# schematic_Func_Gen.net
KiCad netlist of a schematic drawn in Altium Designer
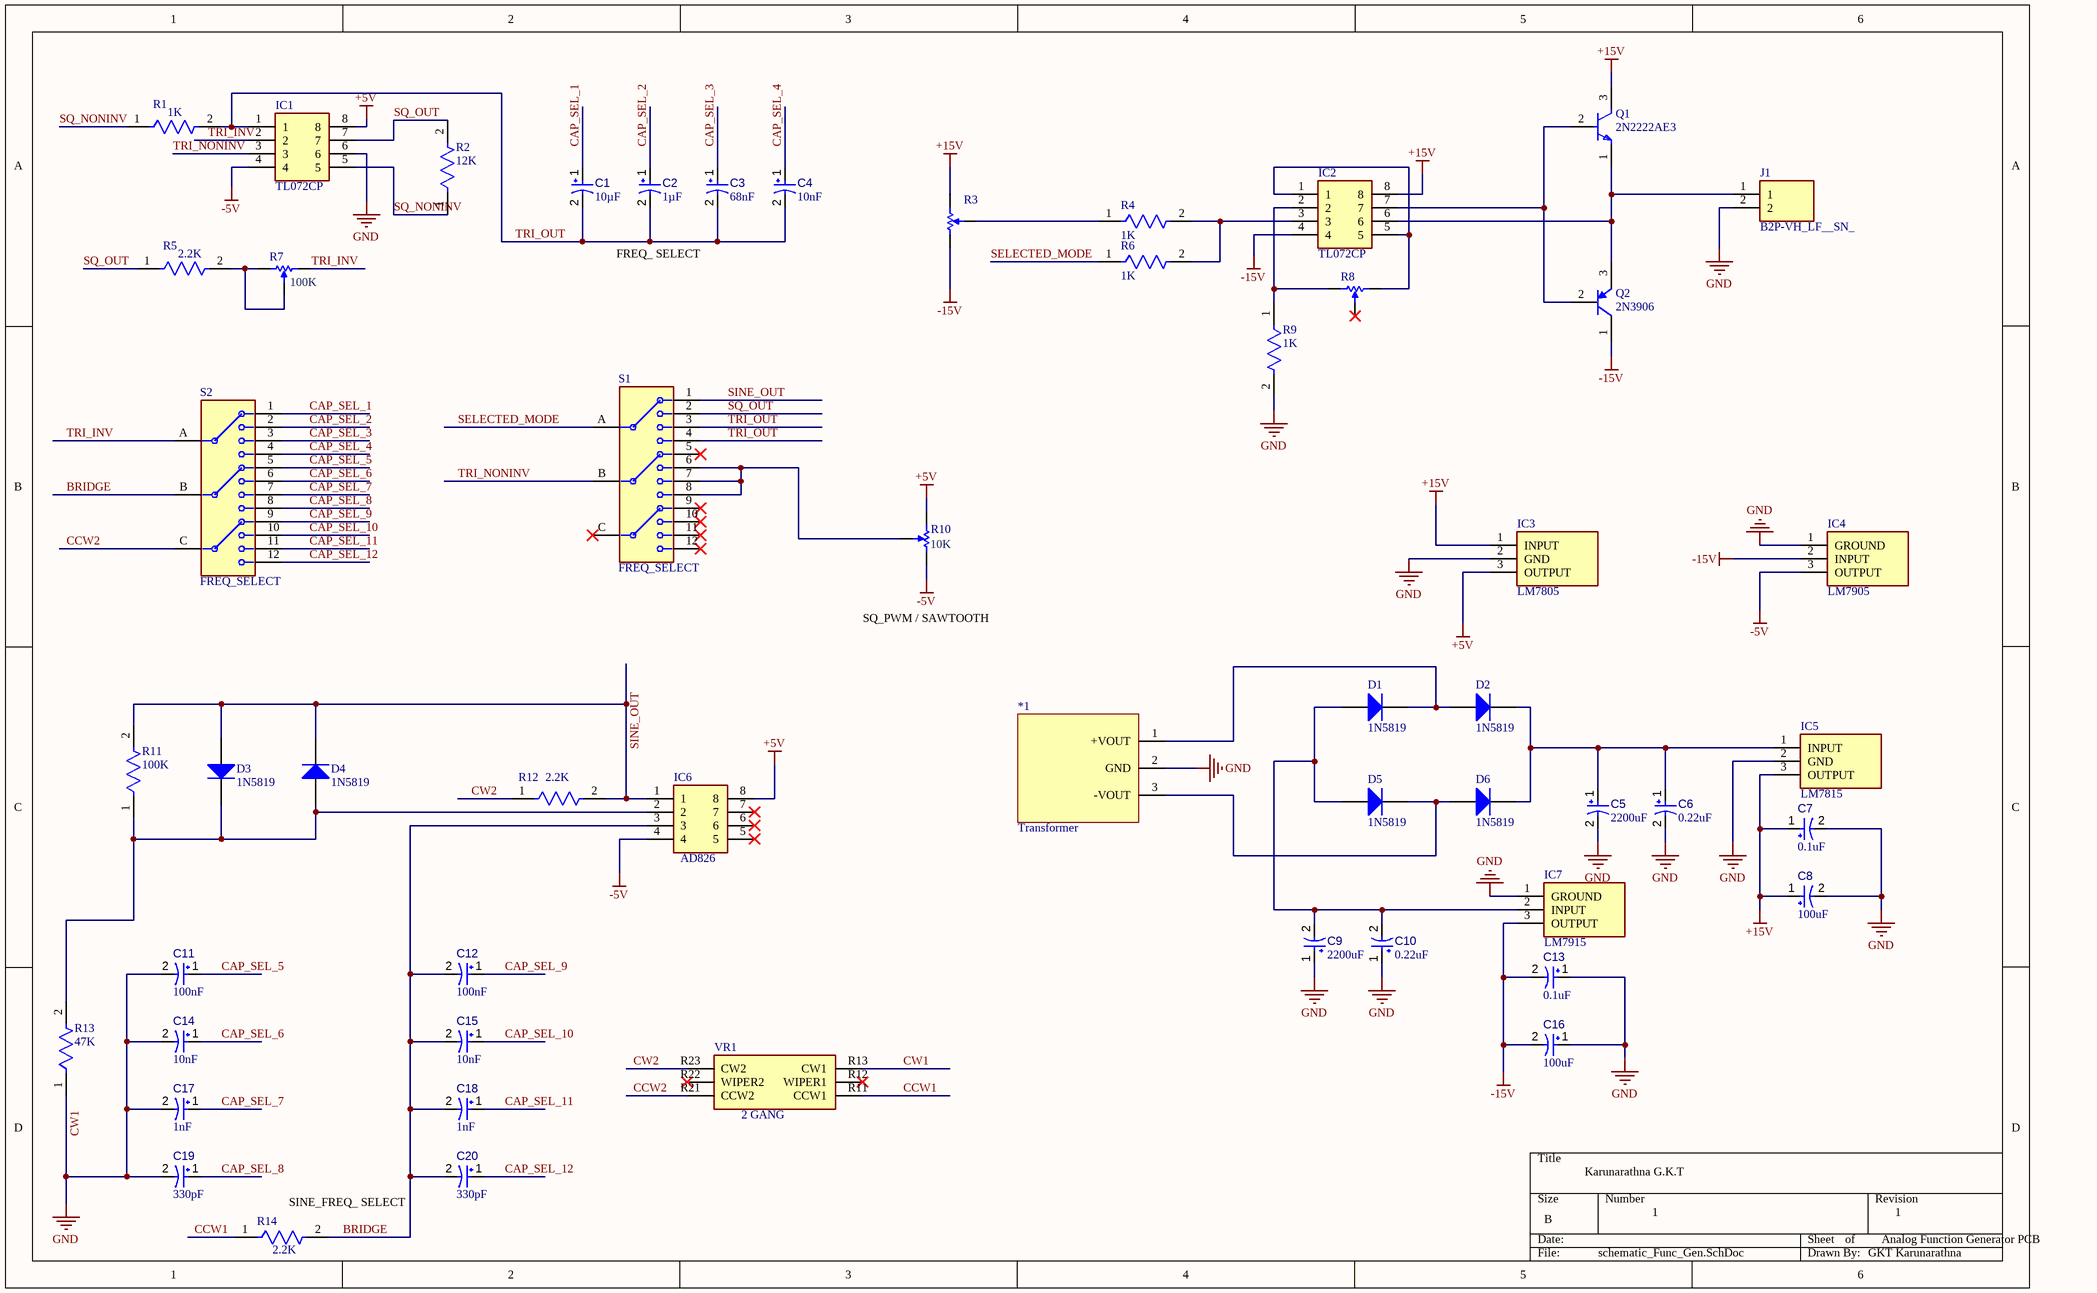
[diagram p0: schematic_Func_Gen.SchDoc]

(export (version "E")
  (design (tool "Eeschema 10.0.6"))
  (components
    (comp (ref "*1")
      (value "Transformer")
      (footprint "transformer")
      (libsource (lib "Schlib") (part "Transformer"))
    )
    (comp (ref "C1")
      (value "10µF")
      (footprint "CAPPR65-500-1250X1000X1350")
      (description "Aluminum Electrolytic Capacitor, 220 uF, +/- 20%, 50 V, -40 to 85 degC, 2-Pin THD, RoHS, Bulk")
      (fields (field (name "MANUFACTURER") "Panasonic") (field (name "TOLERANCE") "20%"))
      (libsource (lib "") (part "CAP-P-2_1"))
    )
    (comp (ref "C2")
      (value "1µF")
      (footprint "CAPPR65-500-1250X1000X1350")
      (description "Aluminum Electrolytic Capacitor, 10 uF, +/- 20%, 50 V, -40 to 85 degC, 2-Pin THD, RoHS, Bulk")
      (fields (field (name "MANUFACTURER") "Panasonic") (field (name "TOLERANCE") "20%"))
      (libsource (lib "") (part "CAP-P-2_1"))
    )
    (comp (ref "C3")
      (value "68nF")
      (footprint "CAPPR65-500-1250X1000X1350")
      (description "Aluminum Electrolytic Capacitor, 220 uF, +/- 20%, 50 V, -40 to 85 degC, 2-Pin THD, RoHS, Bulk")
      (fields (field (name "MANUFACTURER") "Panasonic") (field (name "TOLERANCE") "20%"))
      (libsource (lib "") (part "CAP-P-2_1"))
    )
    (comp (ref "C4")
      (value "10nF")
      (footprint "CAPPR65-500-1250X1000X1350")
      (description "Aluminum Electrolytic Capacitor, 220 uF, +/- 20%, 50 V, -40 to 85 degC, 2-Pin THD, RoHS, Bulk")
      (fields (field (name "MANUFACTURER") "Panasonic") (field (name "TOLERANCE") "20%"))
      (libsource (lib "") (part "CAP-P-2_1"))
    )
    (comp (ref "C5")
      (value "2200uF")
      (footprint "CAPPR65-500-1250X1000X1350")
      (description "Aluminum Electrolytic Capacitor, 220 uF, +/- 20%, 50 V, -40 to 85 degC, 2-Pin THD, RoHS, Bulk")
      (fields (field (name "MANUFACTURER") "Panasonic") (field (name "TOLERANCE") "20%"))
      (libsource (lib "") (part "CAP-P-2_1"))
    )
    (comp (ref "C6")
      (value "0.22uF")
      (footprint "CAPPR65-500-1250X1000X1350")
      (description "Aluminum Electrolytic Capacitor, 220 uF, +/- 20%, 50 V, -40 to 85 degC, 2-Pin THD, RoHS, Bulk")
      (fields (field (name "MANUFACTURER") "Panasonic") (field (name "TOLERANCE") "20%"))
      (libsource (lib "") (part "CAP-P-2_1"))
    )
    (comp (ref "C7")
      (value "0.1uF")
      (footprint "CAPPR65-500-1250X1000X1350")
      (description "Aluminum Electrolytic Capacitor, 220 uF, +/- 20%, 50 V, -40 to 85 degC, 2-Pin THD, RoHS, Bulk")
      (fields (field (name "MANUFACTURER") "Panasonic") (field (name "TOLERANCE") "20%"))
      (libsource (lib "") (part "CAP-P-2_2"))
    )
    (comp (ref "C8")
      (value "100uF")
      (footprint "CAPPR65-500-1250X1000X1350")
      (description "Aluminum Electrolytic Capacitor, 220 uF, +/- 20%, 50 V, -40 to 85 degC, 2-Pin THD, RoHS, Bulk")
      (fields (field (name "MANUFACTURER") "Panasonic") (field (name "TOLERANCE") "20%"))
      (libsource (lib "") (part "CAP-P-2_2"))
    )
    (comp (ref "C9")
      (value "2200uF")
      (footprint "CAPPR65-500-1250X1000X1350")
      (description "Aluminum Electrolytic Capacitor, 220 uF, +/- 20%, 50 V, -40 to 85 degC, 2-Pin THD, RoHS, Bulk")
      (fields (field (name "MANUFACTURER") "Panasonic") (field (name "TOLERANCE") "20%"))
      (libsource (lib "") (part "CAP-P-2_3"))
    )
    (comp (ref "C10")
      (value "0.22uF")
      (footprint "CAPPR65-500-1250X1000X1350")
      (description "Aluminum Electrolytic Capacitor, 220 uF, +/- 20%, 50 V, -40 to 85 degC, 2-Pin THD, RoHS, Bulk")
      (fields (field (name "MANUFACTURER") "Panasonic") (field (name "TOLERANCE") "20%"))
      (libsource (lib "") (part "CAP-P-2_3"))
    )
    (comp (ref "C11")
      (value "100nF")
      (footprint "CAPPR65-500-1250X1000X1350")
      (description "Aluminum Electrolytic Capacitor, 220 uF, +/- 20%, 50 V, -40 to 85 degC, 2-Pin THD, RoHS, Bulk")
      (fields (field (name "MANUFACTURER") "Panasonic") (field (name "TOLERANCE") "20%"))
      (libsource (lib "Kavija Karunarathna") (part "CAP-P-2"))
    )
    (comp (ref "C12")
      (value "100nF")
      (footprint "CAPPR65-500-1250X1000X1350")
      (description "Aluminum Electrolytic Capacitor, 220 uF, +/- 20%, 50 V, -40 to 85 degC, 2-Pin THD, RoHS, Bulk")
      (fields (field (name "MANUFACTURER") "Panasonic") (field (name "TOLERANCE") "20%"))
      (libsource (lib "Kavija Karunarathna") (part "CAP-P-2"))
    )
    (comp (ref "C13")
      (value "0.1uF")
      (footprint "CAPPR65-500-1250X1000X1350")
      (description "Aluminum Electrolytic Capacitor, 220 uF, +/- 20%, 50 V, -40 to 85 degC, 2-Pin THD, RoHS, Bulk")
      (fields (field (name "MANUFACTURER") "Panasonic") (field (name "TOLERANCE") "20%"))
      (libsource (lib "Kavija Karunarathna") (part "CAP-P-2"))
    )
    (comp (ref "C14")
      (value "10nF")
      (footprint "CAPPR65-500-1250X1000X1350")
      (description "Aluminum Electrolytic Capacitor, 220 uF, +/- 20%, 50 V, -40 to 85 degC, 2-Pin THD, RoHS, Bulk")
      (fields (field (name "MANUFACTURER") "Panasonic") (field (name "TOLERANCE") "20%"))
      (libsource (lib "Kavija Karunarathna") (part "CAP-P-2"))
    )
    (comp (ref "C15")
      (value "10nF")
      (footprint "CAPPR65-500-1250X1000X1350")
      (description "Aluminum Electrolytic Capacitor, 220 uF, +/- 20%, 50 V, -40 to 85 degC, 2-Pin THD, RoHS, Bulk")
      (fields (field (name "MANUFACTURER") "Panasonic") (field (name "TOLERANCE") "20%"))
      (libsource (lib "Kavija Karunarathna") (part "CAP-P-2"))
    )
    (comp (ref "C16")
      (value "100uF")
      (footprint "CAPPR65-500-1250X1000X1350")
      (description "Aluminum Electrolytic Capacitor, 220 uF, +/- 20%, 50 V, -40 to 85 degC, 2-Pin THD, RoHS, Bulk")
      (fields (field (name "MANUFACTURER") "Panasonic") (field (name "TOLERANCE") "20%"))
      (libsource (lib "Kavija Karunarathna") (part "CAP-P-2"))
    )
    (comp (ref "C17")
      (value "1nF")
      (footprint "CAPPR65-500-1250X1000X1350")
      (description "Aluminum Electrolytic Capacitor, 220 uF, +/- 20%, 50 V, -40 to 85 degC, 2-Pin THD, RoHS, Bulk")
      (fields (field (name "MANUFACTURER") "Panasonic") (field (name "TOLERANCE") "20%"))
      (libsource (lib "Kavija Karunarathna") (part "CAP-P-2"))
    )
    (comp (ref "C18")
      (value "1nF")
      (footprint "CAPPR65-500-1250X1000X1350")
      (description "Aluminum Electrolytic Capacitor, 220 uF, +/- 20%, 50 V, -40 to 85 degC, 2-Pin THD, RoHS, Bulk")
      (fields (field (name "MANUFACTURER") "Panasonic") (field (name "TOLERANCE") "20%"))
      (libsource (lib "Kavija Karunarathna") (part "CAP-P-2"))
    )
    (comp (ref "C19")
      (value "330pF")
      (footprint "CAPPR65-500-1250X1000X1350")
      (description "Aluminum Electrolytic Capacitor, 220 uF, +/- 20%, 50 V, -40 to 85 degC, 2-Pin THD, RoHS, Bulk")
      (fields (field (name "MANUFACTURER") "Panasonic") (field (name "TOLERANCE") "20%"))
      (libsource (lib "Kavija Karunarathna") (part "CAP-P-2"))
    )
    (comp (ref "C20")
      (value "330pF")
      (footprint "CAPPR65-500-1250X1000X1350")
      (description "Aluminum Electrolytic Capacitor, 220 uF, +/- 20%, 50 V, -40 to 85 degC, 2-Pin THD, RoHS, Bulk")
      (fields (field (name "MANUFACTURER") "Panasonic") (field (name "TOLERANCE") "20%"))
      (libsource (lib "Kavija Karunarathna") (part "CAP-P-2"))
    )
    (comp (ref "D1")
      (value "1N5819")
      (footprint "ONSC-AXIAL_LEAD-2-59-10_P")
      (description "Low Drop Power Schottky Rectifier, 40 V, 1 A, 2-Pin DO-41, RoHS")
      (fields (field (name "MANUFACTURER") "ON Semiconductor"))
      (libsource (lib "Kavija Karunarathna") (part "D-AK-2"))
    )
    (comp (ref "D2")
      (value "1N5819")
      (footprint "ONSC-AXIAL_LEAD-2-59-10_P")
      (description "Low Drop Power Schottky Rectifier, 40 V, 1 A, 2-Pin DO-41, RoHS")
      (fields (field (name "MANUFACTURER") "ON Semiconductor"))
      (libsource (lib "Kavija Karunarathna") (part "D-AK-2"))
    )
    (comp (ref "D3")
      (value "1N5819")
      (footprint "ONSC-AXIAL_LEAD-2-59-10_P")
      (description "Low Drop Power Schottky Rectifier, 40 V, 1 A, 2-Pin DO-41, RoHS")
      (fields (field (name "MANUFACTURER") "ON Semiconductor"))
      (libsource (lib "Kavija Karunarathna") (part "D-AK-2"))
    )
    (comp (ref "D4")
      (value "1N5819")
      (footprint "ONSC-AXIAL_LEAD-2-59-10_P")
      (description "Low Drop Power Schottky Rectifier, 40 V, 1 A, 2-Pin DO-41, RoHS")
      (fields (field (name "MANUFACTURER") "ON Semiconductor"))
      (libsource (lib "Kavija Karunarathna") (part "D-AK-2"))
    )
    (comp (ref "D5")
      (value "1N5819")
      (footprint "ONSC-AXIAL_LEAD-2-59-10_P")
      (description "Low Drop Power Schottky Rectifier, 40 V, 1 A, 2-Pin DO-41, RoHS")
      (fields (field (name "MANUFACTURER") "ON Semiconductor"))
      (libsource (lib "Kavija Karunarathna") (part "D-AK-2"))
    )
    (comp (ref "D6")
      (value "1N5819")
      (footprint "ONSC-AXIAL_LEAD-2-59-10_P")
      (description "Low Drop Power Schottky Rectifier, 40 V, 1 A, 2-Pin DO-41, RoHS")
      (fields (field (name "MANUFACTURER") "ON Semiconductor"))
      (libsource (lib "Kavija Karunarathna") (part "D-AK-2"))
    )
    (comp (ref "IC1")
      (value "TL072CP")
      (footprint "SamacSys:DIPS762W70P254L1016H510Q8N")
      (description "Integrated Circuit")
      (fields
        (field (name "MANUFACTURER_PART_NUMBER") "1-2199298-2")
        (field (name "MOUSER PART NUMBER") "571-1-2199298-2")
      )
      (libsource (lib "*") (part "1-2199298-2"))
    )
    (comp (ref "IC2")
      (value "TL072CP")
      (footprint "SamacSys:DIPS762W70P254L1016H510Q8N")
      (description "Integrated Circuit")
      (fields
        (field (name "MANUFACTURER_PART_NUMBER") "1-2199298-2")
        (field (name "MOUSER PART NUMBER") "571-1-2199298-2")
      )
      (libsource (lib "*") (part "1-2199298-2"))
    )
    (comp (ref "IC3")
      (value "LM7805")
      (footprint "SamacSys:TO254P470X990X1900-3P")
      (description "Integrated Circuit")
      (libsource (lib "*") (part "LM7805"))
    )
    (comp (ref "IC4")
      (value "LM7905")
      (footprint "SamacSys:TO254P470X1028X1955-3P")
      (description "Integrated Circuit")
      (fields
        (field (name "MANUFACTURER_PART_NUMBER") "LM7905CT")
        (field (name "MOUSER PART NUMBER") "926-LM7905CT")
      )
      (libsource (lib "*") (part "LM7905CT"))
    )
    (comp (ref "IC5")
      (value "LM7815")
      (footprint "SamacSys:TO254P470X990X1900-3P")
      (description "Integrated Circuit")
      (fields (field (name "MANUFACTURER_PART_NUMBER") "LM7805"))
      (libsource (lib "*") (part "LM7805"))
    )
    (comp (ref "IC6")
      (value "AD826")
      (footprint "SamacSys:DIPS762W70P254L1016H510Q8N")
      (description "Integrated Circuit")
      (fields
        (field (name "MANUFACTURER_PART_NUMBER") "1-2199298-2")
        (field (name "MOUSER PART NUMBER") "571-1-2199298-2")
      )
      (libsource (lib "*") (part "1-2199298-2"))
    )
    (comp (ref "IC7")
      (value "LM7915")
      (footprint "SamacSys:TO254P470X1028X1955-3P")
      (description "Integrated Circuit")
      (fields
        (field (name "MANUFACTURER_PART_NUMBER") "LM7905CT")
        (field (name "MOUSER PART NUMBER") "926-LM7905CT")
      )
      (libsource (lib "*") (part "LM7905CT"))
    )
    (comp (ref "J1")
      (value "B2P-VH_LF__SN_")
      (footprint "SamacSys:HDRV2W114P0X396_1X2_786X850X1090P")
      (description "Connector")
      (fields (field (name "MANUFACTURER_PART_NUMBER") "B2P-VH(LF)(SN)"))
      (libsource (lib "*") (part "B2P-VH_LF__SN_"))
    )
    (comp (ref "Q1")
      (value "2N2222AE3")
      (footprint "FP-TO-18-MFG")
      (description "2N2222AE3 Bipolar (BJT) Transistor NPN 50V 800mA 500mW Through Hole TO-18")
      (libsource (lib "Altium Content Vault") (part "0adf1720dacd0b636365b40e7c27fbb"))
    )
    (comp (ref "Q2")
      (value "2N3906")
      (footprint "ONSC-TO-92-3-29-11_AM_BL")
      (description "Amplifier Transistor, PNP Silicon, 3-Pin TO-92, Pb-Free, Ammo Box")
      (fields (field (name "PARTNUMBER") "BC557AZL1G") (field (name "MANUFACTURER") "On Semiconductor"))
      (libsource (lib "Altium Content Vault") (part "ONSC-PNP-C1B2E3-3"))
    )
    (comp (ref "R1")
      (value "1K")
      (footprint "FP-RLR07-MFG")
      (description "RLR07C15R0FSB14 Res Metal Film 15 Ohm 1% 1/4W ±100ppm/°C 0.001% Conformal AXL Thru-Hole Bulk")
      (fields (field (name "TOLERANCE") "1%"))
      (libsource (lib "Altium Content Vault") (part "1029c3af85768c4190bb7ad29bc67b5"))
    )
    (comp (ref "R2")
      (value "12K")
      (footprint "FP-RLR07-MFG")
      (description "RLR07C15R0FSB14 Res Metal Film 15 Ohm 1% 1/4W ±100ppm/°C 0.001% Conformal AXL Thru-Hole Bulk")
      (fields (field (name "TOLERANCE") "1%"))
      (libsource (lib "Altium Content Vault") (part "1029c3af85768c4190bb7ad29bc67b5"))
    )
    (comp (ref "R3")
      (value "TC33X-2-103E")
      (footprint "BOUR-TC33X-2_V")
      (description "Trimming Potentiometer, 10000 Ohm, -40 to 100 degC, 3-Pin SMD, RoHS, Tape and Reel")
      (fields (field (name "TOLERANCE") "25%") (field (name "MANUFACTURER") "Bourns"))
      (libsource (lib "Kavija Karunarathna") (part "RES-ADJ-3_A"))
    )
    (comp (ref "R4")
      (value "1K")
      (footprint "FP-RLR07-MFG")
      (description "RLR07C15R0FSB14 Res Metal Film 15 Ohm 1% 1/4W ±100ppm/°C 0.001% Conformal AXL Thru-Hole Bulk")
      (fields (field (name "TOLERANCE") "1%"))
      (libsource (lib "Altium Content Vault") (part "1029c3af85768c4190bb7ad29bc67b5"))
    )
    (comp (ref "R5")
      (value "2.2K")
      (footprint "FP-RLR07-MFG")
      (description "RLR07C15R0FSB14 Res Metal Film 15 Ohm 1% 1/4W ±100ppm/°C 0.001% Conformal AXL Thru-Hole Bulk")
      (fields (field (name "TOLERANCE") "1%"))
      (libsource (lib "Altium Content Vault") (part "1029c3af85768c4190bb7ad29bc67b5"))
    )
    (comp (ref "R6")
      (value "1K")
      (footprint "FP-RLR07-MFG")
      (description "RLR07C15R0FSB14 Res Metal Film 15 Ohm 1% 1/4W ±100ppm/°C 0.001% Conformal AXL Thru-Hole Bulk")
      (fields (field (name "TOLERANCE") "1%"))
      (libsource (lib "Altium Content Vault") (part "1029c3af85768c4190bb7ad29bc67b5"))
    )
    (comp (ref "R7")
      (value "TC33X-2-103E")
      (footprint "BOUR-TC33X-2_V")
      (description "Trimming Potentiometer, 10000 Ohm, -40 to 100 degC, 3-Pin SMD, RoHS, Tape and Reel")
      (fields (field (name "TOLERANCE") "25%") (field (name "MANUFACTURER") "Bourns"))
      (libsource (lib "Kavija Karunarathna") (part "RES-ADJ-3_A"))
    )
    (comp (ref "R8")
      (value "TC33X-2-103E")
      (footprint "BOUR-TC33X-2_V")
      (description "Trimming Potentiometer, 10000 Ohm, -40 to 100 degC, 3-Pin SMD, RoHS, Tape and Reel")
      (fields (field (name "TOLERANCE") "25%") (field (name "MANUFACTURER") "Bourns"))
      (libsource (lib "Kavija Karunarathna") (part "RES-ADJ-3_A"))
    )
    (comp (ref "R9")
      (value "1K")
      (footprint "FP-RLR07-MFG")
      (description "RLR07C15R0FSB14 Res Metal Film 15 Ohm 1% 1/4W ±100ppm/°C 0.001% Conformal AXL Thru-Hole Bulk")
      (fields (field (name "TOLERANCE") "1%"))
      (libsource (lib "Altium Content Vault") (part "1029c3af85768c4190bb7ad29bc67b5"))
    )
    (comp (ref "R10")
      (value "TC33X-2-103E")
      (footprint "BOUR-TC33X-2_V")
      (description "Trimming Potentiometer, 10000 Ohm, -40 to 100 degC, 3-Pin SMD, RoHS, Tape and Reel")
      (fields (field (name "TOLERANCE") "25%") (field (name "MANUFACTURER") "Bourns"))
      (libsource (lib "Kavija Karunarathna") (part "RES-ADJ-3_A"))
    )
    (comp (ref "R11")
      (value "100K")
      (footprint "FP-RLR07-MFG")
      (description "RLR07C15R0FSB14 Res Metal Film 15 Ohm 1% 1/4W ±100ppm/°C 0.001% Conformal AXL Thru-Hole Bulk")
      (fields (field (name "TOLERANCE") "1%"))
      (libsource (lib "Altium Content Vault") (part "1029c3af85768c4190bb7ad29bc67b5"))
    )
    (comp (ref "R12")
      (value "2.2K")
      (footprint "FP-RLR07-MFG")
      (description "RLR07C15R0FSB14 Res Metal Film 15 Ohm 1% 1/4W ±100ppm/°C 0.001% Conformal AXL Thru-Hole Bulk")
      (fields (field (name "TOLERANCE") "1%"))
      (libsource (lib "Altium Content Vault") (part "1029c3af85768c4190bb7ad29bc67b5"))
    )
    (comp (ref "R13")
      (value "47K")
      (footprint "FP-RLR07-MFG")
      (description "RLR07C15R0FSB14 Res Metal Film 15 Ohm 1% 1/4W ±100ppm/°C 0.001% Conformal AXL Thru-Hole Bulk")
      (fields (field (name "TOLERANCE") "1%"))
      (libsource (lib "Altium Content Vault") (part "1029c3af85768c4190bb7ad29bc67b5"))
    )
    (comp (ref "R14")
      (value "2.2K")
      (footprint "FP-RLR07-MFG")
      (description "RLR07C15R0FSB14 Res Metal Film 15 Ohm 1% 1/4W ±100ppm/°C 0.001% Conformal AXL Thru-Hole Bulk")
      (fields (field (name "TOLERANCE") "1%"))
      (libsource (lib "Altium Content Vault") (part "1029c3af85768c4190bb7ad29bc67b5"))
    )
    (comp (ref "S1")
      (value "FREQ_SELECT")
      (footprint "SW_A30403RNCQ")
      (description "Rotary Switch 4 Position 3P4T 2.5A (AC), 350mA (DC) 125 VAC Panel Mount, Through Hole")
      (fields (field (name "MF") "C&K") (field (name "MP") "A30403RNCQ"))
      (libsource (lib "Schlib") (part "A30403RNCQ"))
    )
    (comp (ref "S2")
      (value "FREQ_SELECT")
      (footprint "SW_A30403RNCQ")
      (description "Rotary Switch 4 Position 3P4T 2.5A (AC), 350mA (DC) 125 VAC Panel Mount, Through Hole")
      (fields (field (name "MF") "C&K") (field (name "MP") "A30403RNCQ"))
      (libsource (lib "Schlib") (part "A30403RNCQ"))
    )
    (comp (ref "VR1")
      (value "2 GANG")
      (footprint "SamacSys:PDB182K220K104B")
      (description "Variable Resistor")
      (fields
        (field (name "MANUFACTURER_PART_NUMBER") "PDB182-K220K-104B")
        (field (name "MOUSER PART NUMBER") "652-PDB182-K220K104B")
      )
      (libsource (lib "*") (part "PDB182-K220K-104B"))
    )
  )
  (nets
    (net (code "1") (name "+5V") (class "Default")
      (node (ref "IC1") (pin "8") (pinfunction "8_8") (pintype "passive"))
      (node (ref "IC3") (pin "3") (pinfunction "OUTPUT_3") (pintype "passive"))
      (node (ref "IC6") (pin "8") (pinfunction "8_8") (pintype "passive"))
      (node (ref "R10") (pin "1") (pinfunction "1_1") (pintype "passive"))
    )
    (net (code "2") (name "+15V") (class "Default")
      (node (ref "C7") (pin "1") (pinfunction "1_1") (pintype "passive"))
      (node (ref "C8") (pin "1") (pinfunction "1_1") (pintype "passive"))
      (node (ref "IC2") (pin "8") (pinfunction "8_8") (pintype "passive"))
      (node (ref "IC3") (pin "1") (pinfunction "INPUT_1") (pintype "passive"))
      (node (ref "IC5") (pin "3") (pinfunction "OUTPUT_3") (pintype "passive"))
      (node (ref "Q1") (pin "3") (pinfunction "C_3") (pintype "passive"))
      (node (ref "R3") (pin "3") (pinfunction "3_3") (pintype "passive"))
    )
    (net (code "3") (name "-5V") (class "Default")
      (node (ref "IC1") (pin "4") (pinfunction "4_4") (pintype "passive"))
      (node (ref "IC4") (pin "3") (pinfunction "OUTPUT_3") (pintype "passive"))
      (node (ref "IC6") (pin "4") (pinfunction "4_4") (pintype "passive"))
      (node (ref "R10") (pin "3") (pinfunction "3_3") (pintype "passive"))
    )
    (net (code "4") (name "-15V") (class "Default")
      (node (ref "C13") (pin "2") (pinfunction "2_2") (pintype "passive"))
      (node (ref "C16") (pin "2") (pinfunction "2_2") (pintype "passive"))
      (node (ref "IC2") (pin "4") (pinfunction "4_4") (pintype "passive"))
      (node (ref "IC4") (pin "2") (pinfunction "INPUT_2") (pintype "passive"))
      (node (ref "IC7") (pin "3") (pinfunction "OUTPUT_3") (pintype "passive"))
      (node (ref "Q2") (pin "1") (pinfunction "C_1") (pintype "passive"))
      (node (ref "R3") (pin "1") (pinfunction "1_1") (pintype "passive"))
    )
    (net (code "5") (name "/BRIDGE") (class "Default")
      (node (ref "C12") (pin "2") (pinfunction "2_2") (pintype "passive"))
      (node (ref "C15") (pin "2") (pinfunction "2_2") (pintype "passive"))
      (node (ref "C18") (pin "2") (pinfunction "2_2") (pintype "passive"))
      (node (ref "C20") (pin "2") (pinfunction "2_2") (pintype "passive"))
      (node (ref "IC6") (pin "3") (pinfunction "3_3") (pintype "passive"))
      (node (ref "R14") (pin "2") (pinfunction "2_2") (pintype "passive"))
      (node (ref "S2") (pin "B") (pinfunction "B_B") (pintype "passive"))
    )
    (net (code "6") (name "/CAP_SEL_1") (class "Default")
      (node (ref "C1") (pin "1") (pinfunction "1_1") (pintype "passive"))
      (node (ref "S2") (pin "1") (pinfunction "1_1") (pintype "passive"))
    )
    (net (code "7") (name "/CAP_SEL_2") (class "Default")
      (node (ref "C2") (pin "1") (pinfunction "1_1") (pintype "passive"))
      (node (ref "S2") (pin "2") (pinfunction "2_2") (pintype "passive"))
    )
    (net (code "8") (name "/CAP_SEL_3") (class "Default")
      (node (ref "C3") (pin "1") (pinfunction "1_1") (pintype "passive"))
      (node (ref "S2") (pin "3") (pinfunction "3_3") (pintype "passive"))
    )
    (net (code "9") (name "/CAP_SEL_4") (class "Default")
      (node (ref "C4") (pin "1") (pinfunction "1_1") (pintype "passive"))
      (node (ref "S2") (pin "4") (pinfunction "4_4") (pintype "passive"))
    )
    (net (code "10") (name "/CAP_SEL_5") (class "Default")
      (node (ref "C11") (pin "1") (pinfunction "1_1") (pintype "passive"))
      (node (ref "S2") (pin "5") (pinfunction "5_5") (pintype "passive"))
    )
    (net (code "11") (name "/CAP_SEL_6") (class "Default")
      (node (ref "C14") (pin "1") (pinfunction "1_1") (pintype "passive"))
      (node (ref "S2") (pin "6") (pinfunction "6_6") (pintype "passive"))
    )
    (net (code "12") (name "/CAP_SEL_7") (class "Default")
      (node (ref "C17") (pin "1") (pinfunction "1_1") (pintype "passive"))
      (node (ref "S2") (pin "7") (pinfunction "7_7") (pintype "passive"))
    )
    (net (code "13") (name "/CAP_SEL_8") (class "Default")
      (node (ref "C19") (pin "1") (pinfunction "1_1") (pintype "passive"))
      (node (ref "S2") (pin "8") (pinfunction "8_8") (pintype "passive"))
    )
    (net (code "14") (name "/CAP_SEL_9") (class "Default")
      (node (ref "C12") (pin "1") (pinfunction "1_1") (pintype "passive"))
      (node (ref "S2") (pin "9") (pinfunction "9_9") (pintype "passive"))
    )
    (net (code "15") (name "/CAP_SEL_10") (class "Default")
      (node (ref "C15") (pin "1") (pinfunction "1_1") (pintype "passive"))
      (node (ref "S2") (pin "10") (pinfunction "10_10") (pintype "passive"))
    )
    (net (code "16") (name "/CAP_SEL_11") (class "Default")
      (node (ref "C18") (pin "1") (pinfunction "1_1") (pintype "passive"))
      (node (ref "S2") (pin "11") (pinfunction "11_11") (pintype "passive"))
    )
    (net (code "17") (name "/CAP_SEL_12") (class "Default")
      (node (ref "C20") (pin "1") (pinfunction "1_1") (pintype "passive"))
      (node (ref "S2") (pin "12") (pinfunction "12_12") (pintype "passive"))
    )
    (net (code "18") (name "/CCW1") (class "Default")
      (node (ref "R14") (pin "1") (pinfunction "1_1") (pintype "passive"))
      (node (ref "VR1") (pin "R11") (pinfunction "CCW1_R11") (pintype "passive"))
    )
    (net (code "19") (name "/CCW2") (class "Default")
      (node (ref "S2") (pin "C") (pinfunction "C_C") (pintype "passive"))
      (node (ref "VR1") (pin "R21") (pinfunction "CCW2_R21") (pintype "passive"))
    )
    (net (code "20") (name "/CW2") (class "Default")
      (node (ref "R12") (pin "1") (pinfunction "1_1") (pintype "passive"))
      (node (ref "VR1") (pin "R23") (pinfunction "CW2_R23") (pintype "passive"))
    )
    (net (code "21") (name "/SELECTED_MODE") (class "Default")
      (node (ref "R6") (pin "1") (pinfunction "1_1") (pintype "passive"))
      (node (ref "S1") (pin "A") (pinfunction "A_A") (pintype "passive"))
    )
    (net (code "22") (name "/SINE_OUT") (class "Default")
      (node (ref "D3") (pin "1") (pinfunction "A_1") (pintype "passive"))
      (node (ref "D4") (pin "2") (pinfunction "K_2") (pintype "passive"))
      (node (ref "IC6") (pin "1") (pinfunction "1_1") (pintype "passive"))
      (node (ref "R11") (pin "2") (pinfunction "2_2") (pintype "passive"))
      (node (ref "R12") (pin "2") (pinfunction "2_2") (pintype "passive"))
      (node (ref "S1") (pin "1") (pinfunction "1_1") (pintype "passive"))
    )
    (net (code "23") (name "/SQ_NONINV") (class "Default")
      (node (ref "IC1") (pin "5") (pinfunction "5_5") (pintype "passive"))
      (node (ref "R1") (pin "1") (pinfunction "1_1") (pintype "passive"))
      (node (ref "R2") (pin "1") (pinfunction "1_1") (pintype "passive"))
    )
    (net (code "24") (name "/SQ_OUT") (class "Default")
      (node (ref "IC1") (pin "7") (pinfunction "7_7") (pintype "passive"))
      (node (ref "R2") (pin "2") (pinfunction "2_2") (pintype "passive"))
      (node (ref "R5") (pin "1") (pinfunction "1_1") (pintype "passive"))
      (node (ref "S1") (pin "2") (pinfunction "2_2") (pintype "passive"))
    )
    (net (code "25") (name "/TRI_INV") (class "Default")
      (node (ref "IC1") (pin "2") (pinfunction "2_2") (pintype "passive"))
      (node (ref "R7") (pin "3") (pinfunction "3_3") (pintype "passive"))
      (node (ref "S2") (pin "A") (pinfunction "A_A") (pintype "passive"))
    )
    (net (code "26") (name "/TRI_NONINV") (class "Default")
      (node (ref "IC1") (pin "3") (pinfunction "3_3") (pintype "passive"))
      (node (ref "S1") (pin "B") (pinfunction "B_B") (pintype "passive"))
    )
    (net (code "27") (name "/TRI_OUT") (class "Default")
      (node (ref "C1") (pin "2") (pinfunction "2_2") (pintype "passive"))
      (node (ref "C2") (pin "2") (pinfunction "2_2") (pintype "passive"))
      (node (ref "C3") (pin "2") (pinfunction "2_2") (pintype "passive"))
      (node (ref "C4") (pin "2") (pinfunction "2_2") (pintype "passive"))
      (node (ref "IC1") (pin "1") (pinfunction "1_1") (pintype "passive"))
      (node (ref "R1") (pin "2") (pinfunction "2_2") (pintype "passive"))
      (node (ref "S1") (pin "3") (pinfunction "3_3") (pintype "passive"))
      (node (ref "S1") (pin "4") (pinfunction "4_4") (pintype "passive"))
    )
    (net (code "28") (name "GND") (class "Default")
      (node (ref "*1") (pin "2") (pinfunction "GND_2") (pintype "passive"))
      (node (ref "C10") (pin "1") (pinfunction "1_1") (pintype "passive"))
      (node (ref "C11") (pin "2") (pinfunction "2_2") (pintype "passive"))
      (node (ref "C13") (pin "1") (pinfunction "1_1") (pintype "passive"))
      (node (ref "C14") (pin "2") (pinfunction "2_2") (pintype "passive"))
      (node (ref "C16") (pin "1") (pinfunction "1_1") (pintype "passive"))
      (node (ref "C17") (pin "2") (pinfunction "2_2") (pintype "passive"))
      (node (ref "C19") (pin "2") (pinfunction "2_2") (pintype "passive"))
      (node (ref "C5") (pin "2") (pinfunction "2_2") (pintype "passive"))
      (node (ref "C6") (pin "2") (pinfunction "2_2") (pintype "passive"))
      (node (ref "C7") (pin "2") (pinfunction "2_2") (pintype "passive"))
      (node (ref "C8") (pin "2") (pinfunction "2_2") (pintype "passive"))
      (node (ref "C9") (pin "1") (pinfunction "1_1") (pintype "passive"))
      (node (ref "IC1") (pin "6") (pinfunction "6_6") (pintype "passive"))
      (node (ref "IC3") (pin "2") (pinfunction "GND_2") (pintype "passive"))
      (node (ref "IC4") (pin "1") (pinfunction "GROUND_1") (pintype "passive"))
      (node (ref "IC5") (pin "2") (pinfunction "GND_2") (pintype "passive"))
      (node (ref "IC7") (pin "1") (pinfunction "GROUND_1") (pintype "passive"))
      (node (ref "J1") (pin "2") (pinfunction "2_2") (pintype "passive"))
      (node (ref "R13") (pin "1") (pinfunction "1_1") (pintype "passive"))
      (node (ref "R9") (pin "2") (pinfunction "2_2") (pintype "passive"))
      (node (ref "VR1") (pin "R13") (pinfunction "CW1_R13") (pintype "passive"))
    )
    (net (code "29") (name "Net-(*1-+VOUT)") (class "Default")
      (node (ref "*1") (pin "1") (pinfunction "+VOUT_1") (pintype "passive"))
      (node (ref "D1") (pin "2") (pinfunction "K_2") (pintype "passive"))
      (node (ref "D2") (pin "1") (pinfunction "A_1") (pintype "passive"))
    )
    (net (code "30") (name "Net-(*1--VOUT)") (class "Default")
      (node (ref "*1") (pin "3") (pinfunction "-VOUT_3") (pintype "passive"))
      (node (ref "D5") (pin "2") (pinfunction "K_2") (pintype "passive"))
      (node (ref "D6") (pin "1") (pinfunction "A_1") (pintype "passive"))
    )
    (net (code "31") (name "Net-(D1-A)") (class "Default")
      (node (ref "C10") (pin "2") (pinfunction "2_2") (pintype "passive"))
      (node (ref "C9") (pin "2") (pinfunction "2_2") (pintype "passive"))
      (node (ref "D1") (pin "1") (pinfunction "A_1") (pintype "passive"))
      (node (ref "D5") (pin "1") (pinfunction "A_1") (pintype "passive"))
      (node (ref "IC7") (pin "2") (pinfunction "INPUT_2") (pintype "passive"))
    )
    (net (code "32") (name "Net-(D2-K)") (class "Default")
      (node (ref "C5") (pin "1") (pinfunction "1_1") (pintype "passive"))
      (node (ref "C6") (pin "1") (pinfunction "1_1") (pintype "passive"))
      (node (ref "D2") (pin "2") (pinfunction "K_2") (pintype "passive"))
      (node (ref "D6") (pin "2") (pinfunction "K_2") (pintype "passive"))
      (node (ref "IC5") (pin "1") (pinfunction "INPUT_1") (pintype "passive"))
    )
    (net (code "33") (name "Net-(D3-K)") (class "Default")
      (node (ref "D3") (pin "2") (pinfunction "K_2") (pintype "passive"))
      (node (ref "D4") (pin "1") (pinfunction "A_1") (pintype "passive"))
      (node (ref "IC6") (pin "2") (pinfunction "2_2") (pintype "passive"))
      (node (ref "R11") (pin "1") (pinfunction "1_1") (pintype "passive"))
      (node (ref "R13") (pin "2") (pinfunction "2_2") (pintype "passive"))
    )
    (net (code "34") (name "Net-(IC2-Pad1)") (class "Default")
      (node (ref "IC2") (pin "1") (pinfunction "1_1") (pintype "passive"))
      (node (ref "IC2") (pin "5") (pinfunction "5_5") (pintype "passive"))
      (node (ref "R8") (pin "3") (pinfunction "3_3") (pintype "passive"))
    )
    (net (code "35") (name "Net-(IC2-Pad2)") (class "Default")
      (node (ref "IC2") (pin "2") (pinfunction "2_2") (pintype "passive"))
      (node (ref "R8") (pin "1") (pinfunction "1_1") (pintype "passive"))
      (node (ref "R9") (pin "1") (pinfunction "1_1") (pintype "passive"))
    )
    (net (code "36") (name "Net-(IC2-Pad3)") (class "Default")
      (node (ref "IC2") (pin "3") (pinfunction "3_3") (pintype "passive"))
      (node (ref "R4") (pin "2") (pinfunction "2_2") (pintype "passive"))
      (node (ref "R6") (pin "2") (pinfunction "2_2") (pintype "passive"))
    )
    (net (code "37") (name "Net-(Q1-B)") (class "Default")
      (node (ref "IC2") (pin "7") (pinfunction "7_7") (pintype "passive"))
      (node (ref "Q1") (pin "2") (pinfunction "B_2") (pintype "passive"))
      (node (ref "Q2") (pin "2") (pinfunction "B_2") (pintype "passive"))
    )
    (net (code "38") (name "Net-(Q1-E)") (class "Default")
      (node (ref "IC2") (pin "6") (pinfunction "6_6") (pintype "passive"))
      (node (ref "J1") (pin "1") (pinfunction "1_1") (pintype "passive"))
      (node (ref "Q1") (pin "1") (pinfunction "E_1") (pintype "passive"))
      (node (ref "Q2") (pin "3") (pinfunction "E_3") (pintype "passive"))
    )
    (net (code "39") (name "Net-(R3-Pad2)") (class "Default")
      (node (ref "R3") (pin "2") (pinfunction "2_2") (pintype "passive"))
      (node (ref "R4") (pin "1") (pinfunction "1_1") (pintype "passive"))
    )
    (net (code "40") (name "Net-(R5-Pad2)") (class "Default")
      (node (ref "R5") (pin "2") (pinfunction "2_2") (pintype "passive"))
      (node (ref "R7") (pin "1") (pinfunction "1_1") (pintype "passive"))
      (node (ref "R7") (pin "2") (pinfunction "2_2") (pintype "passive"))
    )
    (net (code "41") (name "Net-(R10-Pad2)") (class "Default")
      (node (ref "R10") (pin "2") (pinfunction "2_2") (pintype "passive"))
      (node (ref "S1") (pin "6") (pinfunction "6_6") (pintype "passive"))
      (node (ref "S1") (pin "7") (pinfunction "7_7") (pintype "passive"))
      (node (ref "S1") (pin "8") (pinfunction "8_8") (pintype "passive"))
    )
    (net (code "42") (name "unconnected-(IC6-Pad5)") (class "Default")
      (node (ref "IC6") (pin "5") (pinfunction "5_5") (pintype "passive+no_connect"))
    )
    (net (code "43") (name "unconnected-(IC6-Pad6)") (class "Default")
      (node (ref "IC6") (pin "6") (pinfunction "6_6") (pintype "passive+no_connect"))
    )
    (net (code "44") (name "unconnected-(IC6-Pad7)") (class "Default")
      (node (ref "IC6") (pin "7") (pinfunction "7_7") (pintype "passive+no_connect"))
    )
    (net (code "45") (name "unconnected-(R8-Pad2)") (class "Default")
      (node (ref "R8") (pin "2") (pinfunction "2_2") (pintype "passive+no_connect"))
    )
    (net (code "46") (name "unconnected-(S1-Pad5)") (class "Default")
      (node (ref "S1") (pin "5") (pinfunction "5_5") (pintype "passive+no_connect"))
    )
    (net (code "47") (name "unconnected-(S1-Pad9)") (class "Default")
      (node (ref "S1") (pin "9") (pinfunction "9_9") (pintype "passive+no_connect"))
    )
    (net (code "48") (name "unconnected-(S1-Pad10)") (class "Default")
      (node (ref "S1") (pin "10") (pinfunction "10_10") (pintype "passive+no_connect"))
    )
    (net (code "49") (name "unconnected-(S1-Pad11)") (class "Default")
      (node (ref "S1") (pin "11") (pinfunction "11_11") (pintype "passive+no_connect"))
    )
    (net (code "50") (name "unconnected-(S1-Pad12)") (class "Default")
      (node (ref "S1") (pin "12") (pinfunction "12_12") (pintype "passive+no_connect"))
    )
    (net (code "51") (name "unconnected-(S1-PadC)") (class "Default")
      (node (ref "S1") (pin "C") (pinfunction "C_C") (pintype "passive+no_connect"))
    )
    (net (code "52") (name "unconnected-(VR1-WIPER1-PadR12)") (class "Default")
      (node (ref "VR1") (pin "R12") (pinfunction "WIPER1_R12") (pintype "passive+no_connect"))
    )
    (net (code "53") (name "unconnected-(VR1-WIPER2-PadR22)") (class "Default")
      (node (ref "VR1") (pin "R22") (pinfunction "WIPER2_R22") (pintype "passive+no_connect"))
    )
  )
)
